# DisplayPort.net
KiCad netlist of a schematic drawn in Altium Designer
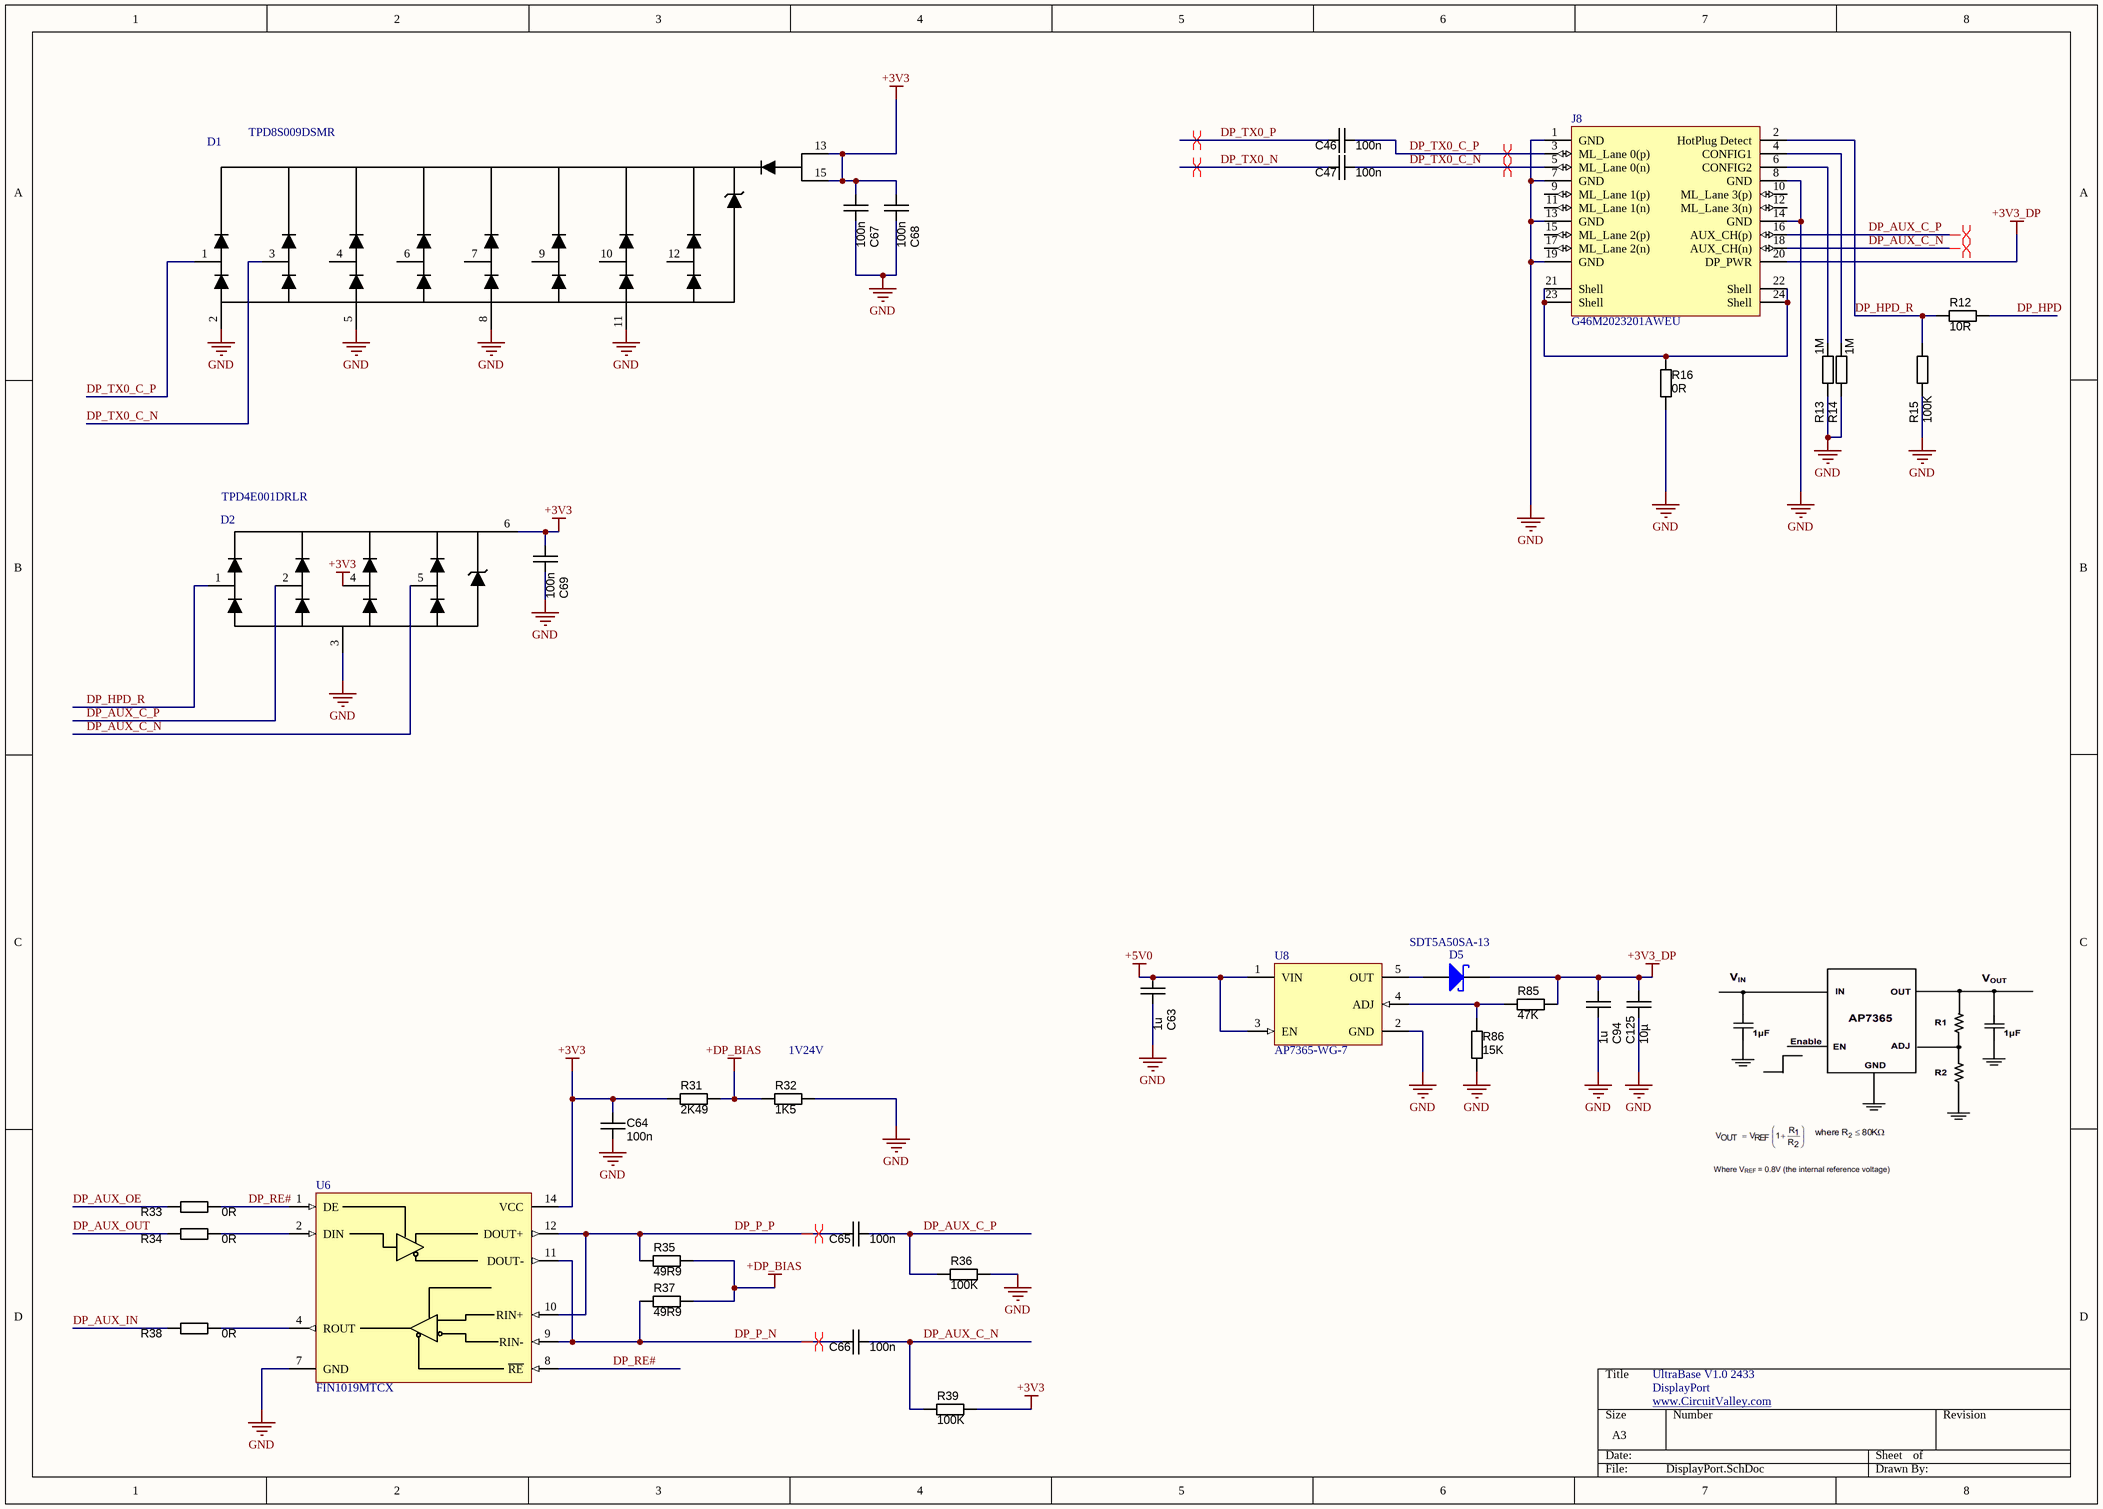
[diagram p0: DisplayPort.SchDoc]

(export (version "E")
  (design (tool "Eeschema 10.0.6"))
  (components
    (comp (ref "C46")
      (value "100n")
      (footprint "CAPC1005N")
      (description "Capacitor SMD Cer 100nF 10% 16V X5R 0402")
      (fields (field (name "TOLERANCE") "±10%"))
      (libsource (lib "PBL - Capacitors") (part "CAPC_100n_0402_16V_10%"))
    )
    (comp (ref "C47")
      (value "100n")
      (footprint "CAPC1005N")
      (description "Capacitor SMD Cer 100nF 10% 16V X5R 0402")
      (fields (field (name "TOLERANCE") "±10%"))
      (libsource (lib "PBL - Capacitors") (part "CAPC_100n_0402_16V_10%"))
    )
    (comp (ref "C63")
      (value "1u")
      (footprint "CAPC1608N")
      (description "Capacitor SMD Cer 120pF 10% 50V C0G 0603")
      (fields (field (name "TOLERANCE") "±10%"))
      (libsource (lib "PBL - Capacitors") (part "CAPC_120p_0603_C0G_50V"))
    )
    (comp (ref "C64")
      (value "100n")
      (footprint "CAPC1608N")
      (description "Capacitor SMD Cer 1nF 10% 100V X7R 0603")
      (fields (field (name "TOLERANCE") "±10%"))
      (libsource (lib "PBL - Capacitors") (part "CAPC_1n_0603_100V"))
    )
    (comp (ref "C65")
      (value "100n")
      (footprint "CAPC1005N")
      (description "Capacitor SMD Cer 100nF 10% 16V X5R 0402")
      (fields (field (name "TOLERANCE") "±10%"))
      (libsource (lib "PBL - Capacitors") (part "CAPC_100n_0402_16V_10%"))
    )
    (comp (ref "C66")
      (value "100n")
      (footprint "CAPC1005N")
      (description "Capacitor SMD Cer 100nF 10% 16V X5R 0402")
      (fields (field (name "TOLERANCE") "±10%"))
      (libsource (lib "PBL - Capacitors") (part "CAPC_100n_0402_16V_10%"))
    )
    (comp (ref "C67")
      (value "100n")
      (footprint "CAPC1608N")
      (description "Capacitor SMD Cer 120pF 10% 50V C0G 0603")
      (fields (field (name "TOLERANCE") "±10%"))
      (libsource (lib "PBL - Capacitors") (part "CAPC_120p_0603_C0G_50V"))
    )
    (comp (ref "C68")
      (value "100n")
      (footprint "CAPC1608N")
      (description "Capacitor SMD Cer 120pF 10% 50V C0G 0603")
      (fields (field (name "TOLERANCE") "±10%"))
      (libsource (lib "PBL - Capacitors") (part "CAPC_120p_0603_C0G_50V"))
    )
    (comp (ref "C69")
      (value "100n")
      (footprint "CAPC1608N")
      (description "Capacitor SMD Cer 120pF 10% 50V C0G 0603")
      (fields (field (name "TOLERANCE") "±10%"))
      (libsource (lib "PBL - Capacitors") (part "CAPC_120p_0603_C0G_50V"))
    )
    (comp (ref "C94")
      (value "1u")
      (footprint "CAPC1608N")
      (description "Capacitor SMD Cer 120pF 10% 50V C0G 0603")
      (fields (field (name "TOLERANCE") "±10%"))
      (libsource (lib "PBL - Capacitors") (part "CAPC_120p_0603_C0G_50V"))
    )
    (comp (ref "C125")
      (value "10µ")
      (footprint "CAPC3225N")
      (description "Capacitor SMD Cer 10uF 20% 16V X5R 1210")
      (fields (field (name "TOLERANCE") "±20%"))
      (libsource (lib "PBL - Capacitors") (part "CAPC_10u_1210_50V"))
    )
    (comp (ref "D1")
      (value "TPD8S009DSMR")
      (footprint "WSON-15")
      (description "Display Port ESD")
      (libsource (lib "cvlib") (part "TPD8S009DSMR"))
    )
    (comp (ref "D2")
      (value "TPD4E001DRLR")
      (footprint "SOT5x3")
      (description "ESD Protection")
      (libsource (lib "cvlib") (part "TPD4E001DRLR"))
    )
    (comp (ref "D5")
      (value "SDT5A50SA-13")
      (footprint "DO-214AC")
      (description "Diode")
      (libsource (lib "cvlib") (part "Diode"))
    )
    (comp (ref "J8")
      (value "G46M2023201AWEU")
      (footprint "G46M2023201AWEU")
      (description "Mini Display Port")
      (libsource (lib "cvlib") (part "G46M2023201AWEU"))
    )
    (comp (ref "R12")
      (value "10R")
      (footprint "RESC1608N")
      (description "Resistor, SMD chip")
      (fields (field (name "TOLERANCE") "±5%") (field (name "Comment") "RES_NL_0603"))
      (libsource (lib "PBL - Resistors") (part "RES_NL_0603"))
    )
    (comp (ref "R13")
      (value "1M")
      (footprint "RESC1608N")
      (description "Resistor, SMD chip")
      (fields (field (name "TOLERANCE") "±5%") (field (name "Comment") "RES_NL_0603"))
      (libsource (lib "") (part "RES_NL_0603_1"))
    )
    (comp (ref "R14")
      (value "1M")
      (footprint "RESC1608N")
      (description "Resistor, SMD chip")
      (fields (field (name "TOLERANCE") "±5%") (field (name "Comment") "RES_NL_0603"))
      (libsource (lib "") (part "RES_NL_0603_1"))
    )
    (comp (ref "R15")
      (value "100K")
      (footprint "RESC1608N")
      (description "Resistor, SMD chip")
      (fields (field (name "TOLERANCE") "±5%") (field (name "Comment") "RES_NL_0603"))
      (libsource (lib "") (part "RES_NL_0603_1"))
    )
    (comp (ref "R16")
      (value "0R")
      (footprint "RESC1608N")
      (description "Resistor, SMD chip")
      (fields (field (name "TOLERANCE") "±5%") (field (name "Comment") "RES_NL_0603"))
      (libsource (lib "") (part "RES_NL_0603_1"))
    )
    (comp (ref "R31")
      (value "2K49")
      (footprint "RESC1608N")
      (description "Resistor, SMD chip")
      (fields (field (name "TOLERANCE") "±5%") (field (name "Comment") "RES_NL_0603"))
      (libsource (lib "PBL - Resistors") (part "RES_NL_0603"))
    )
    (comp (ref "R32")
      (value "1K5")
      (footprint "RESC1608N")
      (description "Resistor, SMD chip")
      (fields (field (name "TOLERANCE") "±5%") (field (name "Comment") "RES_NL_0603"))
      (libsource (lib "PBL - Resistors") (part "RES_NL_0603"))
    )
    (comp (ref "R33")
      (value "0R")
      (footprint "RESC1608N")
      (description "Resistor, SMD chip")
      (fields (field (name "TOLERANCE") "±5%") (field (name "Comment") "RES_NL_0603"))
      (libsource (lib "PBL - Resistors") (part "RES_NL_0603"))
    )
    (comp (ref "R34")
      (value "0R")
      (footprint "RESC1608N")
      (description "Resistor, SMD chip")
      (fields (field (name "TOLERANCE") "±5%") (field (name "Comment") "RES_NL_0603"))
      (libsource (lib "PBL - Resistors") (part "RES_NL_0603"))
    )
    (comp (ref "R35")
      (value "49R9")
      (footprint "RESC1608N")
      (description "Resistor, SMD chip")
      (fields (field (name "TOLERANCE") "±5%") (field (name "Comment") "RES_NL_0603"))
      (libsource (lib "") (part "RES_NL_0603_3"))
    )
    (comp (ref "R36")
      (value "100K")
      (footprint "RESC1608N")
      (description "Resistor, SMD chip")
      (fields (field (name "TOLERANCE") "±5%") (field (name "Comment") "RES_NL_0603"))
      (libsource (lib "") (part "RES_NL_0603_3"))
    )
    (comp (ref "R37")
      (value "49R9")
      (footprint "RESC1608N")
      (description "Resistor, SMD chip")
      (fields (field (name "TOLERANCE") "±5%") (field (name "Comment") "RES_NL_0603"))
      (libsource (lib "PBL - Resistors") (part "RES_NL_0603"))
    )
    (comp (ref "R38")
      (value "0R")
      (footprint "RESC1608N")
      (description "Resistor, SMD chip")
      (fields (field (name "TOLERANCE") "±5%") (field (name "Comment") "RES_NL_0603"))
      (libsource (lib "PBL - Resistors") (part "RES_NL_0603"))
    )
    (comp (ref "R39")
      (value "100K")
      (footprint "RESC1608N")
      (description "Resistor, SMD chip")
      (fields (field (name "TOLERANCE") "±5%") (field (name "Comment") "RES_NL_0603"))
      (libsource (lib "") (part "RES_NL_0603_3"))
    )
    (comp (ref "R85")
      (value "47K")
      (footprint "RESC1608N")
      (description "Resistor, SMD chip")
      (fields (field (name "TOLERANCE") "±5%") (field (name "Comment") "RES_NL_0603"))
      (libsource (lib "PBL - Resistors") (part "RES_NL_0603"))
    )
    (comp (ref "R86")
      (value "15K")
      (footprint "RESC1608N")
      (description "Resistor, SMD chip")
      (fields (field (name "TOLERANCE") "±5%") (field (name "Comment") "RES_NL_0603"))
      (libsource (lib "") (part "RES_NL_0603_2"))
    )
    (comp (ref "U6")
      (value "FIN1019MTCX")
      (footprint "TSSOP14 PW G14")
      (description "Differential Buffer")
      (libsource (lib "cvlib") (part "FIN1019MTCX"))
    )
    (comp (ref "U8")
      (value "AP7365-WG-7")
      (footprint "SOT23-5")
      (description "LDO Reg ADJ 600mA")
      (libsource (lib "cvlib") (part "AP7365-WG-7"))
    )
  )
  (nets
    (net (code "1") (name "+3V3") (class "Default")
      (node (ref "C64") (pin "1") (pintype "passive"))
      (node (ref "C67") (pin "1") (pintype "passive"))
      (node (ref "C68") (pin "1") (pintype "passive"))
      (node (ref "C69") (pin "1") (pintype "passive"))
      (node (ref "D1") (pin "13") (pinfunction "13_13") (pintype "power_in"))
      (node (ref "D1") (pin "15") (pinfunction "15_15") (pintype "power_in"))
      (node (ref "D2") (pin "4") (pinfunction "4_4") (pintype "passive"))
      (node (ref "D2") (pin "6") (pinfunction "6_6") (pintype "power_in"))
      (node (ref "R31") (pin "1") (pinfunction "1_1") (pintype "passive"))
      (node (ref "R39") (pin "1") (pinfunction "1_1") (pintype "passive"))
      (node (ref "U6") (pin "14") (pinfunction "VCC_14") (pintype "power_in"))
    )
    (net (code "2") (name "+3V3_DP") (class "Default")
      (node (ref "C125") (pin "1") (pintype "passive"))
      (node (ref "C94") (pin "1") (pintype "passive"))
      (node (ref "D5") (pin "2") (pinfunction "K_2") (pintype "passive"))
      (node (ref "J8") (pin "20") (pinfunction "DP_PWR_20") (pintype "power_in"))
      (node (ref "R85") (pin "2") (pinfunction "2_2") (pintype "passive"))
    )
    (net (code "3") (name "+5V0") (class "Default")
      (node (ref "C63") (pin "1") (pintype "passive"))
      (node (ref "U8") (pin "1") (pinfunction "VIN_1") (pintype "power_in"))
      (node (ref "U8") (pin "3") (pinfunction "EN_3") (pintype "input"))
    )
    (net (code "4") (name "+DP_BIAS") (class "Default")
      (node (ref "R31") (pin "2") (pinfunction "2_2") (pintype "passive"))
      (node (ref "R32") (pin "1") (pinfunction "1_1") (pintype "passive"))
      (node (ref "R35") (pin "1") (pinfunction "1_1") (pintype "passive"))
      (node (ref "R37") (pin "2") (pinfunction "2_2") (pintype "passive"))
    )
    (net (code "5") (name "/DP_AUX_C_N") (class "Default")
      (node (ref "C66") (pin "2") (pintype "passive"))
      (node (ref "D2") (pin "5") (pinfunction "5_5") (pintype "passive"))
      (node (ref "J8") (pin "18") (pinfunction "AUX_CH(n)_18") (pintype "bidirectional"))
      (node (ref "R39") (pin "2") (pinfunction "2_2") (pintype "passive"))
    )
    (net (code "6") (name "/DP_AUX_C_P") (class "Default")
      (node (ref "C65") (pin "2") (pintype "passive"))
      (node (ref "D2") (pin "2") (pinfunction "2_2") (pintype "passive"))
      (node (ref "J8") (pin "16") (pinfunction "AUX_CH(p)_16") (pintype "bidirectional"))
      (node (ref "R36") (pin "2") (pinfunction "2_2") (pintype "passive"))
    )
    (net (code "7") (name "/DP_AUX_IN") (class "Default")
      (node (ref "R38") (pin "1") (pinfunction "1_1") (pintype "passive"))
    )
    (net (code "8") (name "/DP_AUX_OE") (class "Default")
      (node (ref "R33") (pin "1") (pinfunction "1_1") (pintype "passive"))
    )
    (net (code "9") (name "/DP_AUX_OUT") (class "Default")
      (node (ref "R34") (pin "1") (pinfunction "1_1") (pintype "passive"))
    )
    (net (code "10") (name "/DP_HPD") (class "Default")
      (node (ref "R12") (pin "2") (pinfunction "2_2") (pintype "passive"))
    )
    (net (code "11") (name "/DP_HPD_R") (class "Default")
      (node (ref "D2") (pin "1") (pinfunction "1_1") (pintype "passive"))
      (node (ref "J8") (pin "2") (pinfunction "HotPlug_Detect_2") (pintype "passive"))
      (node (ref "R12") (pin "1") (pinfunction "1_1") (pintype "passive"))
      (node (ref "R15") (pin "1") (pinfunction "1_1") (pintype "passive"))
    )
    (net (code "12") (name "/DP_P_N") (class "Default")
      (node (ref "C66") (pin "1") (pintype "passive"))
      (node (ref "R37") (pin "1") (pinfunction "1_1") (pintype "passive"))
      (node (ref "U6") (pin "11") (pinfunction "DOUT-_11") (pintype "output"))
      (node (ref "U6") (pin "9") (pinfunction "RIN-_9") (pintype "input"))
    )
    (net (code "13") (name "/DP_P_P") (class "Default")
      (node (ref "C65") (pin "1") (pintype "passive"))
      (node (ref "R35") (pin "2") (pinfunction "2_2") (pintype "passive"))
      (node (ref "U6") (pin "10") (pinfunction "RIN+_10") (pintype "input"))
      (node (ref "U6") (pin "12") (pinfunction "DOUT+_12") (pintype "output"))
    )
    (net (code "14") (name "/DP_RE#") (class "Default")
      (node (ref "R33") (pin "2") (pinfunction "2_2") (pintype "passive"))
      (node (ref "U6") (pin "1") (pinfunction "DE_1") (pintype "input"))
      (node (ref "U6") (pin "8") (pinfunction "~{RE}_8") (pintype "input"))
    )
    (net (code "15") (name "/DP_TX0_C_N") (class "Default")
      (node (ref "C47") (pin "2") (pintype "passive"))
      (node (ref "D1") (pin "3") (pinfunction "3_3") (pintype "passive"))
      (node (ref "J8") (pin "5") (pinfunction "ML_Lane_0(n)_5") (pintype "bidirectional"))
    )
    (net (code "16") (name "/DP_TX0_C_P") (class "Default")
      (node (ref "C46") (pin "2") (pintype "passive"))
      (node (ref "D1") (pin "1") (pinfunction "1_1") (pintype "passive"))
      (node (ref "J8") (pin "3") (pinfunction "ML_Lane_0(p)_3") (pintype "bidirectional"))
    )
    (net (code "17") (name "/DP_TX0_N") (class "Default") (node (ref "C47") (pin "1") (pintype "passive")))
    (net (code "18") (name "/DP_TX0_P") (class "Default") (node (ref "C46") (pin "1") (pintype "passive")))
    (net (code "19") (name "GND") (class "Default")
      (node (ref "C125") (pin "2") (pintype "passive"))
      (node (ref "C63") (pin "2") (pintype "passive"))
      (node (ref "C64") (pin "2") (pintype "passive"))
      (node (ref "C67") (pin "2") (pintype "passive"))
      (node (ref "C68") (pin "2") (pintype "passive"))
      (node (ref "C69") (pin "2") (pintype "passive"))
      (node (ref "C94") (pin "2") (pintype "passive"))
      (node (ref "D1") (pin "11") (pinfunction "11_11") (pintype "passive"))
      (node (ref "D1") (pin "2") (pinfunction "2_2") (pintype "passive"))
      (node (ref "D1") (pin "5") (pinfunction "5_5") (pintype "passive"))
      (node (ref "D1") (pin "8") (pinfunction "8_8") (pintype "passive"))
      (node (ref "D2") (pin "3") (pinfunction "3_3") (pintype "passive"))
      (node (ref "J8") (pin "1") (pinfunction "GND_1") (pintype "passive"))
      (node (ref "J8") (pin "13") (pinfunction "GND_13") (pintype "passive"))
      (node (ref "J8") (pin "14") (pinfunction "GND_14") (pintype "passive"))
      (node (ref "J8") (pin "19") (pinfunction "GND_19") (pintype "passive"))
      (node (ref "J8") (pin "7") (pinfunction "GND_7") (pintype "passive"))
      (node (ref "J8") (pin "8") (pinfunction "GND_8") (pintype "passive"))
      (node (ref "R13") (pin "2") (pinfunction "2_2") (pintype "passive"))
      (node (ref "R14") (pin "2") (pinfunction "2_2") (pintype "passive"))
      (node (ref "R15") (pin "2") (pinfunction "2_2") (pintype "passive"))
      (node (ref "R16") (pin "2") (pinfunction "2_2") (pintype "passive"))
      (node (ref "R32") (pin "2") (pinfunction "2_2") (pintype "passive"))
      (node (ref "R36") (pin "1") (pinfunction "1_1") (pintype "passive"))
      (node (ref "R86") (pin "1") (pinfunction "1_1") (pintype "passive"))
      (node (ref "U6") (pin "7") (pinfunction "GND_7") (pintype "passive"))
      (node (ref "U8") (pin "2") (pinfunction "GND_2") (pintype "power_in"))
    )
    (net (code "20") (name "Net-(D5-A)") (class "Default")
      (node (ref "D5") (pin "1") (pinfunction "A_1") (pintype "passive"))
      (node (ref "U8") (pin "5") (pinfunction "OUT_5") (pintype "power_in"))
    )
    (net (code "21") (name "Net-(J8-CONFIG1)") (class "Default")
      (node (ref "J8") (pin "4") (pinfunction "CONFIG1_4") (pintype "passive"))
      (node (ref "R14") (pin "1") (pinfunction "1_1") (pintype "passive"))
    )
    (net (code "22") (name "Net-(J8-CONFIG2)") (class "Default")
      (node (ref "J8") (pin "6") (pinfunction "CONFIG2_6") (pintype "passive"))
      (node (ref "R13") (pin "1") (pinfunction "1_1") (pintype "passive"))
    )
    (net (code "23") (name "Net-(J8-Shell-Pad21)") (class "Default")
      (node (ref "J8") (pin "21") (pinfunction "Shell_21") (pintype "power_in"))
      (node (ref "J8") (pin "22") (pinfunction "Shell_22") (pintype "power_in"))
      (node (ref "J8") (pin "23") (pinfunction "Shell_23") (pintype "power_in"))
      (node (ref "J8") (pin "24") (pinfunction "Shell_24") (pintype "power_in"))
      (node (ref "R16") (pin "1") (pinfunction "1_1") (pintype "passive"))
    )
    (net (code "24") (name "Net-(U6-DIN)") (class "Default")
      (node (ref "R34") (pin "2") (pinfunction "2_2") (pintype "passive"))
      (node (ref "U6") (pin "2") (pinfunction "DIN_2") (pintype "input"))
    )
    (net (code "25") (name "Net-(U6-ROUT)") (class "Default")
      (node (ref "R38") (pin "2") (pinfunction "2_2") (pintype "passive"))
      (node (ref "U6") (pin "4") (pinfunction "ROUT_4") (pintype "output"))
    )
    (net (code "26") (name "Net-(U8-ADJ)") (class "Default")
      (node (ref "R85") (pin "1") (pinfunction "1_1") (pintype "passive"))
      (node (ref "R86") (pin "2") (pinfunction "2_2") (pintype "passive"))
      (node (ref "U8") (pin "4") (pinfunction "ADJ_4") (pintype "input"))
    )
    (net (code "27") (name "unconnected-(D1-Pad4)") (class "Default")
      (node (ref "D1") (pin "4") (pinfunction "4_4") (pintype "passive"))
    )
    (net (code "28") (name "unconnected-(D1-Pad6)") (class "Default")
      (node (ref "D1") (pin "6") (pinfunction "6_6") (pintype "passive"))
    )
    (net (code "29") (name "unconnected-(D1-Pad7)") (class "Default")
      (node (ref "D1") (pin "7") (pinfunction "7_7") (pintype "passive"))
    )
    (net (code "30") (name "unconnected-(D1-Pad9)") (class "Default")
      (node (ref "D1") (pin "9") (pinfunction "9_9") (pintype "passive"))
    )
    (net (code "31") (name "unconnected-(D1-Pad10)") (class "Default")
      (node (ref "D1") (pin "10") (pinfunction "10_10") (pintype "passive"))
    )
    (net (code "32") (name "unconnected-(D1-Pad12)") (class "Default")
      (node (ref "D1") (pin "12") (pinfunction "12_12") (pintype "passive"))
    )
    (net (code "33") (name "unconnected-(J8-ML_Lane_1(n)-Pad11)") (class "Default")
      (node (ref "J8") (pin "11") (pinfunction "ML_Lane_1(n)_11") (pintype "bidirectional"))
    )
    (net (code "34") (name "unconnected-(J8-ML_Lane_1(p)-Pad9)") (class "Default")
      (node (ref "J8") (pin "9") (pinfunction "ML_Lane_1(p)_9") (pintype "bidirectional"))
    )
    (net (code "35") (name "unconnected-(J8-ML_Lane_2(n)-Pad17)") (class "Default")
      (node (ref "J8") (pin "17") (pinfunction "ML_Lane_2(n)_17") (pintype "bidirectional"))
    )
    (net (code "36") (name "unconnected-(J8-ML_Lane_2(p)-Pad15)") (class "Default")
      (node (ref "J8") (pin "15") (pinfunction "ML_Lane_2(p)_15") (pintype "bidirectional"))
    )
    (net (code "37") (name "unconnected-(J8-ML_Lane_3(n)-Pad12)") (class "Default")
      (node (ref "J8") (pin "12") (pinfunction "ML_Lane_3(n)_12") (pintype "bidirectional"))
    )
    (net (code "38") (name "unconnected-(J8-ML_Lane_3(p)-Pad10)") (class "Default")
      (node (ref "J8") (pin "10") (pinfunction "ML_Lane_3(p)_10") (pintype "bidirectional"))
    )
  )
)
